# slouchpad_v1_shoulder.net
KiCad netlist of a schematic drawn in EAGLE
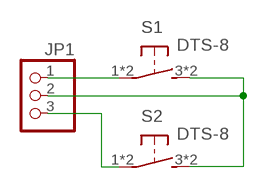
[diagram p0: schematic, sheet 1]

(export (version "E")
  (design (tool "Eeschema 10.0.6"))
  (components
    (comp (ref "JP1")
      (value "PINHD-1X3")
      (footprint "eagle-import:1X03")
      (libsource (lib "eagle-import") (part "PINHD-1X3"))
    )
    (comp (ref "S1")
      (value "DTS-8")
      (footprint "eagle-import:DTS-8")
      (libsource (lib "eagle-import") (part "DTS-8"))
    )
    (comp (ref "S2")
      (value "DTS-8")
      (footprint "eagle-import:DTS-8")
      (libsource (lib "eagle-import") (part "DTS-8"))
    )
  )
  (nets
    (net (code "1") (name "Net-(JP1-Pad1)") (class "Default")
      (node (ref "JP1") (pin "1") (pinfunction "1_1") (pintype "passive"))
      (node (ref "S1") (pin "1") (pinfunction "1_1") (pintype "passive"))
      (node (ref "S1") (pin "2") (pinfunction "1_2") (pintype "passive"))
    )
    (net (code "2") (name "Net-(JP1-Pad2)") (class "Default")
      (node (ref "JP1") (pin "2") (pinfunction "2_2") (pintype "passive"))
      (node (ref "S1") (pin "3") (pinfunction "2_3") (pintype "passive"))
      (node (ref "S1") (pin "4") (pinfunction "2_4") (pintype "passive"))
      (node (ref "S2") (pin "3") (pinfunction "2_3") (pintype "passive"))
      (node (ref "S2") (pin "4") (pinfunction "2_4") (pintype "passive"))
    )
    (net (code "3") (name "Net-(JP1-Pad3)") (class "Default")
      (node (ref "JP1") (pin "3") (pinfunction "3_3") (pintype "passive"))
      (node (ref "S2") (pin "1") (pinfunction "1_1") (pintype "passive"))
      (node (ref "S2") (pin "2") (pinfunction "1_2") (pintype "passive"))
    )
  )
)
